# ComandosExt.net
KiCad netlist of a schematic drawn in Altium Designer
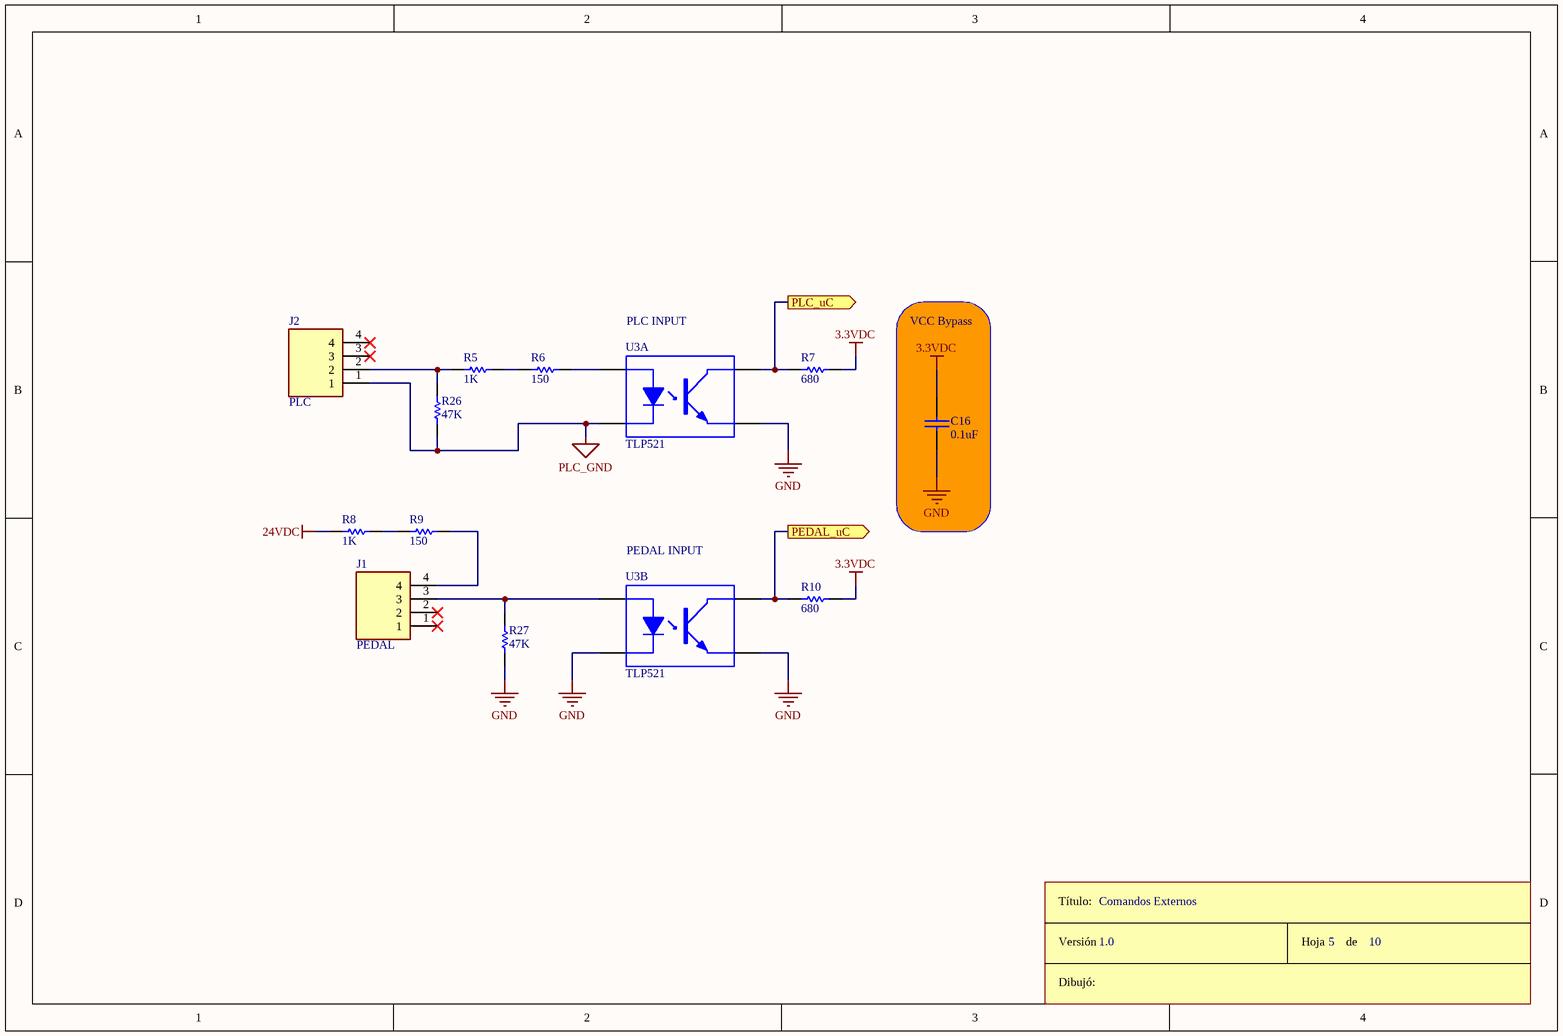
[diagram p0: ComandosExt.SchDoc]

(export (version "E")
  (design (tool "Eeschema 10.0.6"))
  (components
    (comp (ref "C16") (value "0.1uF") (footprint "CAP100") (libsource (lib "LIBEBAL") (part "CAP")))
    (comp (ref "J1")
      (value "PEDAL")
      (footprint "TE_1586863-4")
      (description "Conn Power HDR 4 POS 4.2mm Solder RA Thru-Hole 4 Terminal 1 Port Tray")
      (fields (field (name "MF") "TE Connectivity") (field (name "MP") "1586863-4"))
      (libsource (lib "MFW4R") (part "1586863-4"))
    )
    (comp (ref "J2")
      (value "PLC")
      (footprint "TE_1586863-4")
      (description "Conn Power HDR 4 POS 4.2mm Solder RA Thru-Hole 4 Terminal 1 Port Tray")
      (fields (field (name "MF") "TE Connectivity") (field (name "MP") "1586863-4"))
      (libsource (lib "MFW4R") (part "1586863-4"))
    )
    (comp (ref "R5") (value "1K") (footprint "RES300") (libsource (lib "LIBEBAL") (part "RES")))
    (comp (ref "R6") (value "150") (footprint "RES300") (libsource (lib "LIBEBAL") (part "RES")))
    (comp (ref "R7") (value "680") (footprint "RES300") (libsource (lib "LIBEBAL") (part "RES")))
    (comp (ref "R8") (value "1K") (footprint "RES300") (libsource (lib "LIBEBAL") (part "RES")))
    (comp (ref "R9") (value "150") (footprint "RES300") (libsource (lib "LIBEBAL") (part "RES")))
    (comp (ref "R10") (value "680") (footprint "RES300") (libsource (lib "LIBEBAL") (part "RES")))
    (comp (ref "R26") (value "47K") (footprint "RES300") (libsource (lib "LIBEBAL") (part "RES")))
    (comp (ref "R27") (value "47K") (footprint "RES300") (libsource (lib "LIBEBAL") (part "RES")))
    (comp (ref "ROT3") (value "Rótulo") (libsource (lib "LIB PIO IX") (part "Rótulo")))
    (comp (ref "U3")
      (value "TLP521")
      (footprint "DIP8")
      (description "PhotoCoupler")
      (libsource (lib "AditionalComponents") (part "TLP521-2"))
    )
  )
  (nets
    (net (code "1") (name "/PEDAL_uC") (class "Default")
      (node (ref "R10") (pin "1") (pinfunction "1_1") (pintype "passive"))
      (node (ref "U3") (pin "6") (pinfunction "C_6") (pintype "passive"))
    )
    (net (code "2") (name "/PLC_uC") (class "Default")
      (node (ref "R7") (pin "1") (pinfunction "1_1") (pintype "passive"))
      (node (ref "U3") (pin "8") (pinfunction "C_8") (pintype "passive"))
    )
    (net (code "3") (name "3.3VDC") (class "Default")
      (node (ref "C16") (pin "1") (pinfunction "1_1") (pintype "passive"))
      (node (ref "R10") (pin "2") (pinfunction "2_2") (pintype "passive"))
      (node (ref "R7") (pin "2") (pinfunction "2_2") (pintype "passive"))
    )
    (net (code "4") (name "24VDC") (class "Default")
      (node (ref "R8") (pin "1") (pinfunction "1_1") (pintype "passive"))
    )
    (net (code "5") (name "GND") (class "Default")
      (node (ref "C16") (pin "2") (pinfunction "2_2") (pintype "passive"))
      (node (ref "R27") (pin "1") (pinfunction "1_1") (pintype "passive"))
      (node (ref "U3") (pin "4") (pinfunction "K_4") (pintype "passive"))
      (node (ref "U3") (pin "5") (pinfunction "E_5") (pintype "passive"))
      (node (ref "U3") (pin "7") (pinfunction "E_7") (pintype "passive"))
    )
    (net (code "6") (name "Net-(J1-Pad4)") (class "Default")
      (node (ref "J1") (pin "4") (pinfunction "4_4") (pintype "passive"))
      (node (ref "R9") (pin "2") (pinfunction "2_2") (pintype "passive"))
    )
    (net (code "7") (name "Net-(J2-Pad2)") (class "Default")
      (node (ref "J2") (pin "2") (pinfunction "2_2") (pintype "passive"))
      (node (ref "R26") (pin "2") (pinfunction "2_2") (pintype "passive"))
      (node (ref "R5") (pin "1") (pinfunction "1_1") (pintype "passive"))
    )
    (net (code "8") (name "Net-(R5-Pad2)") (class "Default")
      (node (ref "R5") (pin "2") (pinfunction "2_2") (pintype "passive"))
      (node (ref "R6") (pin "1") (pinfunction "1_1") (pintype "passive"))
    )
    (net (code "9") (name "Net-(R8-Pad2)") (class "Default")
      (node (ref "R8") (pin "2") (pinfunction "2_2") (pintype "passive"))
      (node (ref "R9") (pin "1") (pinfunction "1_1") (pintype "passive"))
    )
    (net (code "10") (name "Net-(U3A-A)") (class "Default")
      (node (ref "R6") (pin "2") (pinfunction "2_2") (pintype "passive"))
      (node (ref "U3") (pin "1") (pinfunction "A_1") (pintype "passive"))
    )
    (net (code "11") (name "Net-(U3B-A)") (class "Default")
      (node (ref "J1") (pin "3") (pinfunction "3_3") (pintype "passive"))
      (node (ref "R27") (pin "2") (pinfunction "2_2") (pintype "passive"))
      (node (ref "U3") (pin "3") (pinfunction "A_3") (pintype "passive"))
    )
    (net (code "12") (name "PLC_GND") (class "Default")
      (node (ref "J2") (pin "1") (pinfunction "1_1") (pintype "passive"))
      (node (ref "R26") (pin "1") (pinfunction "1_1") (pintype "passive"))
      (node (ref "U3") (pin "2") (pinfunction "K_2") (pintype "passive"))
    )
    (net (code "13") (name "unconnected-(J1-Pad1)") (class "Default")
      (node (ref "J1") (pin "1") (pinfunction "1_1") (pintype "passive+no_connect"))
    )
    (net (code "14") (name "unconnected-(J1-Pad2)") (class "Default")
      (node (ref "J1") (pin "2") (pinfunction "2_2") (pintype "passive+no_connect"))
    )
    (net (code "15") (name "unconnected-(J2-Pad3)") (class "Default")
      (node (ref "J2") (pin "3") (pinfunction "3_3") (pintype "passive+no_connect"))
    )
    (net (code "16") (name "unconnected-(J2-Pad4)") (class "Default")
      (node (ref "J2") (pin "4") (pinfunction "4_4") (pintype "passive+no_connect"))
    )
  )
)
